# Motor-Y.net
KiCad netlist of a schematic drawn in Altium Designer
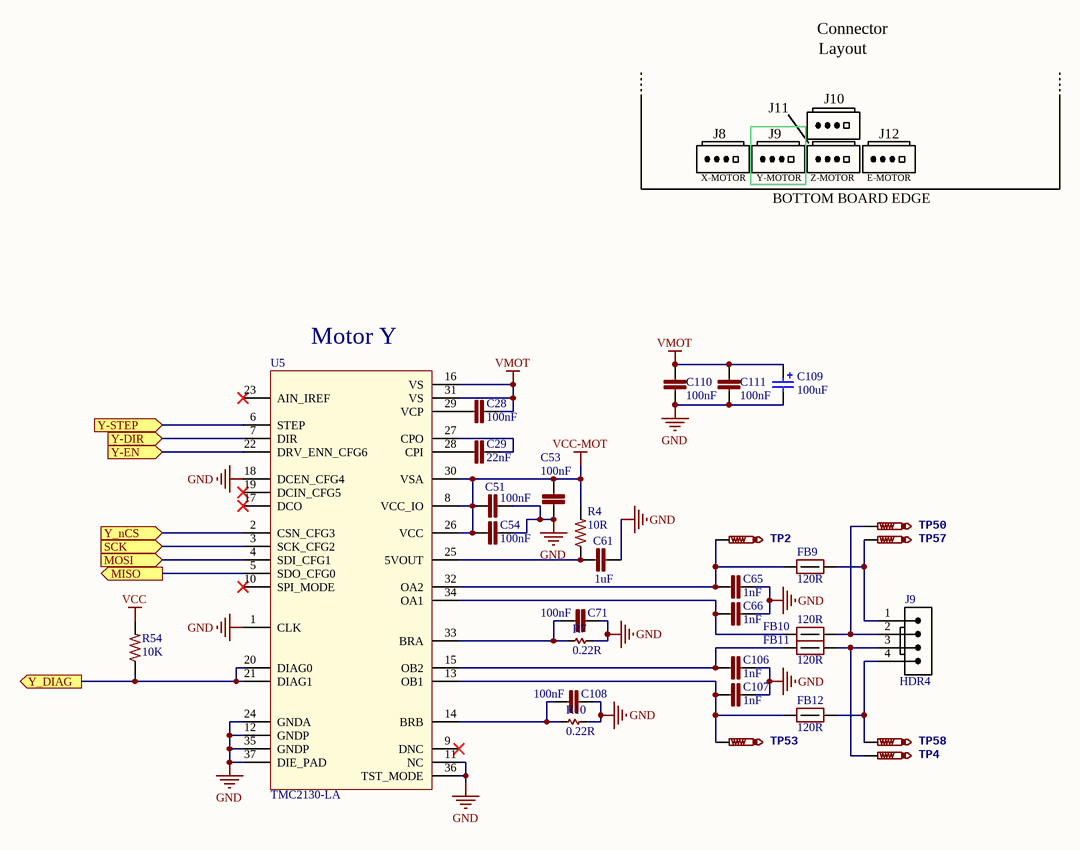
[diagram p0: Motor-Y.SchDoc]

(export (version "E")
  (design (tool "Eeschema 10.0.6"))
  (components
    (comp (ref "C28")
      (value "100nF")
      (footprint "C0603")
      (description "CAP CER 0603 100nF 50V 10% X7R")
      (fields (field (name "MANUFACTURER") "Kemet") (field (name "TOLERANCE") "+/- 10%"))
      (libsource (lib "") (part "C0603C104K5RACTU_2"))
    )
    (comp (ref "C29")
      (value "22nF")
      (footprint "C0402")
      (description "CAP CER 0402 22nF ±10% 50V X7R")
      (fields (field (name "MANUFACTURER") "YAGEO") (field (name "TOLERANCE") "+/- 10%"))
      (libsource (lib "3Delight") (part "GCM155R71H223KA55D"))
    )
    (comp (ref "C51")
      (value "100nF")
      (footprint "C0402")
      (description "CAP CER 0402 100nF 16V 10% X7R")
      (fields (field (name "MANUFACTURER") "Murata") (field (name "TOLERANCE") "+/- 10%"))
      (libsource (lib "3Delight") (part "GRM155R71C104KA88D"))
    )
    (comp (ref "C53")
      (value "100nF")
      (footprint "C0402")
      (description "CAP CER 0402 100nF 16V 10% X7R")
      (fields (field (name "MANUFACTURER") "Murata") (field (name "TOLERANCE") "+/- 10%"))
      (libsource (lib "") (part "GRM155R71C104KA88D_1"))
    )
    (comp (ref "C54")
      (value "100nF")
      (footprint "C0402")
      (description "CAP CER 0402 100nF 16V 10% X7R")
      (fields (field (name "MANUFACTURER") "Murata") (field (name "TOLERANCE") "+/- 10%"))
      (libsource (lib "3Delight") (part "GRM155R71C104KA88D"))
    )
    (comp (ref "C61")
      (value "1uF")
      (footprint "C0402")
      (description "CAP CER 0402 1uF 6.3V 10% X5R")
      (fields (field (name "MANUFACTURER") "Murata") (field (name "TOLERANCE") "+/- 10%"))
      (libsource (lib "3Delight") (part "GRM155R60J105KE19D"))
    )
    (comp (ref "C65")
      (value "1nF")
      (footprint "C0603")
      (description "CAP CER 0603  1nF 50v 10% X7R")
      (fields (field (name "MANUFACTURER") "Kemet") (field (name "TOLERANCE") "+/- 10%"))
      (libsource (lib "3Delight") (part "C0603C102K5RACTU"))
    )
    (comp (ref "C66")
      (value "1nF")
      (footprint "C0603")
      (description "CAP CER 0603  1nF 50v 10% X7R")
      (fields (field (name "MANUFACTURER") "Kemet") (field (name "TOLERANCE") "+/- 10%"))
      (libsource (lib "3Delight") (part "C0603C102K5RACTU"))
    )
    (comp (ref "C71")
      (value "100nF")
      (footprint "C0603")
      (description "CAP CER 0603 100nF 50V 10% X7R")
      (fields (field (name "MANUFACTURER") "Kemet") (field (name "TOLERANCE") "+/- 10%"))
      (libsource (lib "") (part "C0603C104K5RACTU_1"))
    )
    (comp (ref "C106")
      (value "1nF")
      (footprint "C0603")
      (description "CAP CER 0603  1nF 50v 10% X7R")
      (fields (field (name "MANUFACTURER") "Kemet") (field (name "TOLERANCE") "+/- 10%"))
      (libsource (lib "3Delight") (part "C0603C102K5RACTU"))
    )
    (comp (ref "C107")
      (value "1nF")
      (footprint "C0603")
      (description "CAP CER 0603  1nF 50v 10% X7R")
      (fields (field (name "MANUFACTURER") "Kemet") (field (name "TOLERANCE") "+/- 10%"))
      (libsource (lib "3Delight") (part "C0603C102K5RACTU"))
    )
    (comp (ref "C108")
      (value "100nF")
      (footprint "C0603")
      (description "CAP CER 0603 100nF 50V 10% X7R")
      (fields (field (name "MANUFACTURER") "Kemet") (field (name "TOLERANCE") "+/- 10%"))
      (libsource (lib "") (part "C0603C104K5RACTU_1"))
    )
    (comp (ref "C109")
      (value "100uF")
      (footprint "CAP-ELEC-063063077")
      (description "CAP ALUM 100UF 35V 20% SMD")
      (fields (field (name "MANUFACTURER") "Nichicon") (field (name "TOLERANCE") "+/- 20%"))
      (libsource (lib "3Delight") (part "UWT1V101MCL1GS"))
    )
    (comp (ref "C110")
      (value "100nF")
      (footprint "C0603")
      (description "CAP CER 0603 100nF 50V 10% X7R")
      (fields (field (name "MANUFACTURER") "Kemet") (field (name "TOLERANCE") "+/- 10%"))
      (libsource (lib "3Delight") (part "C0603C104K5RACTU"))
    )
    (comp (ref "C111")
      (value "100nF")
      (footprint "C0603")
      (description "CAP CER 0603 100nF 50V 10% X7R")
      (fields (field (name "MANUFACTURER") "Kemet") (field (name "TOLERANCE") "+/- 10%"))
      (libsource (lib "3Delight") (part "C0603C104K5RACTU"))
    )
    (comp (ref "FB9")
      (value "120R")
      (footprint "FB0603")
      (description "FERRITE BEAD 120 OHM 0603 1LN")
      (fields (field (name "MANUFACTURER") "Samsung") (field (name "PART") "FERRITE 120R 3A 0603"))
      (libsource (lib "Inductors") (part "FERRITE 120R 3A 0603"))
    )
    (comp (ref "FB10")
      (value "120R")
      (footprint "FB0603")
      (description "FERRITE BEAD 120 OHM 0603 1LN")
      (fields (field (name "MANUFACTURER") "Samsung") (field (name "PART") "FERRITE 120R 3A 0603"))
      (libsource (lib "Inductors") (part "FERRITE 120R 3A 0603"))
    )
    (comp (ref "FB11")
      (value "120R")
      (footprint "FB0603")
      (description "FERRITE BEAD 120 OHM 0603 1LN")
      (fields (field (name "MANUFACTURER") "Samsung") (field (name "PART") "FERRITE 120R 3A 0603"))
      (libsource (lib "Inductors") (part "FERRITE 120R 3A 0603"))
    )
    (comp (ref "FB12")
      (value "120R")
      (footprint "FB0603")
      (description "FERRITE BEAD 120 OHM 0603 1LN")
      (fields (field (name "MANUFACTURER") "Samsung") (field (name "PART") "FERRITE 120R 3A 0603"))
      (libsource (lib "Inductors") (part "FERRITE 120R 3A 0603"))
    )
    (comp (ref "J9")
      (value "HDR4")
      (footprint "4POL254")
      (description "Molex 4 Pin Clip Connector")
      (fields (field (name "MANUFACTURER") "Molex") (field (name "PART") "4 Pin Conn"))
      (libsource (lib "3Delight") (part "CONN 4PIN 0.1{dblquote} VERT SHRD LOCK ALT"))
    )
    (comp (ref "R4")
      (value "10R")
      (footprint "R0402")
      (description "RES SMD 10 OHM 1% 1/16W 0402")
      (fields (field (name "MANUFACTURER") "Yageo") (field (name "TOLERANCE") "+/- 1%"))
      (libsource (lib "3Delight") (part "RC0402FR-0710RL"))
    )
    (comp (ref "R7")
      (value "0.22R")
      (footprint "R1206")
      (description "RES SMD 0.22 OHM 1% 1/3W 1206")
      (fields (field (name "MANUFACTURER") "Panasonic") (field (name "TOLERANCE") "+/- 1%"))
      (libsource (lib "Resistors") (part "0.22R 1% 1206"))
    )
    (comp (ref "R10")
      (value "0.22R")
      (footprint "R1206")
      (description "RES SMD 0.22 OHM 1% 1/3W 1206")
      (fields (field (name "MANUFACTURER") "Panasonic") (field (name "TOLERANCE") "+/- 1%"))
      (libsource (lib "Resistors") (part "0.22R 1% 1206"))
    )
    (comp (ref "R54")
      (value "10K")
      (footprint "R0402")
      (description "RES SMD 10K OHM 1% 1/16W 0402")
      (fields (field (name "MANUFACTURER") "Yageo") (field (name "PART") "10k 1% 0402"))
      (libsource (lib "3Delight") (part "RC0402FR-0710KP"))
    )
    (comp (ref "TP2")
      (value "TestPoint")
      (footprint "TP1-27")
      (description "Test Point")
      (libsource (lib "3Delight") (part "TestPoint"))
    )
    (comp (ref "TP4")
      (value "TestPoint")
      (footprint "TP1-27")
      (description "Test Point")
      (libsource (lib "3Delight") (part "TestPoint"))
    )
    (comp (ref "TP50")
      (value "TestPoint")
      (footprint "TP1-27")
      (description "Test Point")
      (libsource (lib "3Delight") (part "TestPoint"))
    )
    (comp (ref "TP53")
      (value "TestPoint")
      (footprint "TP1-27")
      (description "Test Point")
      (libsource (lib "3Delight") (part "TestPoint"))
    )
    (comp (ref "TP57")
      (value "TestPoint")
      (footprint "TP1-27")
      (description "Test Point")
      (libsource (lib "3Delight") (part "TestPoint"))
    )
    (comp (ref "TP58")
      (value "TestPoint")
      (footprint "TP1-27")
      (description "Test Point")
      (libsource (lib "3Delight") (part "TestPoint"))
    )
    (comp (ref "U5")
      (value "TMC2130-LA")
      (footprint "QFN36-50P500X600X900_HS-37N")
      (description "IC STEPPER MOTOR DVR SPI 36QFN")
      (fields (field (name "MANUFACTURER") "Trinamic") (field (name "PART") "TMC2130"))
      (libsource (lib "3Delight") (part "TMC2130-LA-T"))
    )
  )
  (nets
    (net (code "1") (name "/MISO") (class "Default")
      (node (ref "U5") (pin "5") (pinfunction "SDO_CFG0_5") (pintype "passive"))
    )
    (net (code "2") (name "/MOSI") (class "Default")
      (node (ref "U5") (pin "4") (pinfunction "SDI_CFG1_4") (pintype "passive"))
    )
    (net (code "3") (name "/SCK") (class "Default")
      (node (ref "U5") (pin "3") (pinfunction "SCK_CFG2_3") (pintype "passive"))
    )
    (net (code "4") (name "/Y-DIR") (class "Default")
      (node (ref "U5") (pin "7") (pinfunction "DIR_7") (pintype "passive"))
    )
    (net (code "5") (name "/Y-EN") (class "Default")
      (node (ref "U5") (pin "22") (pinfunction "DRV_ENN_CFG6_22") (pintype "passive"))
    )
    (net (code "6") (name "/Y-STEP") (class "Default")
      (node (ref "U5") (pin "6") (pinfunction "STEP_6") (pintype "passive"))
    )
    (net (code "7") (name "/Y_DIAG") (class "Default")
      (node (ref "R54") (pin "1") (pinfunction "1_1") (pintype "passive"))
      (node (ref "U5") (pin "20") (pinfunction "DIAG0_20") (pintype "passive"))
      (node (ref "U5") (pin "21") (pinfunction "DIAG1_21") (pintype "passive"))
    )
    (net (code "8") (name "/Y_nCS") (class "Default")
      (node (ref "U5") (pin "2") (pinfunction "CSN_CFG3_2") (pintype "passive"))
    )
    (net (code "9") (name "GND") (class "Default")
      (node (ref "C106") (pin "2") (pinfunction "2_2") (pintype "passive"))
      (node (ref "C107") (pin "2") (pinfunction "2_2") (pintype "passive"))
      (node (ref "C108") (pin "1") (pinfunction "1_1") (pintype "passive"))
      (node (ref "C109") (pin "2") (pinfunction "2_2") (pintype "passive"))
      (node (ref "C110") (pin "1") (pinfunction "1_1") (pintype "passive"))
      (node (ref "C111") (pin "1") (pinfunction "1_1") (pintype "passive"))
      (node (ref "C51") (pin "1") (pinfunction "1_1") (pintype "passive"))
      (node (ref "C53") (pin "1") (pinfunction "1_1") (pintype "passive"))
      (node (ref "C54") (pin "1") (pinfunction "1_1") (pintype "passive"))
      (node (ref "C61") (pin "2") (pinfunction "2_2") (pintype "passive"))
      (node (ref "C65") (pin "2") (pinfunction "2_2") (pintype "passive"))
      (node (ref "C66") (pin "2") (pinfunction "2_2") (pintype "passive"))
      (node (ref "C71") (pin "1") (pinfunction "1_1") (pintype "passive"))
      (node (ref "R10") (pin "2") (pinfunction "2_2") (pintype "passive"))
      (node (ref "R7") (pin "2") (pinfunction "2_2") (pintype "passive"))
      (node (ref "U5") (pin "1") (pinfunction "CLK_1") (pintype "passive"))
      (node (ref "U5") (pin "11") (pinfunction "NC_11") (pintype "passive"))
      (node (ref "U5") (pin "12") (pinfunction "GNDP_12") (pintype "passive"))
      (node (ref "U5") (pin "18") (pinfunction "DCEN_CFG4_18") (pintype "passive"))
      (node (ref "U5") (pin "24") (pinfunction "GNDA_24") (pintype "passive"))
      (node (ref "U5") (pin "35") (pinfunction "GNDP_35") (pintype "passive"))
      (node (ref "U5") (pin "36") (pinfunction "TST_MODE_36") (pintype "passive"))
      (node (ref "U5") (pin "37") (pinfunction "DIE_PAD_37") (pintype "passive"))
    )
    (net (code "10") (name "Net-(FB9-Pad2)") (class "Default")
      (node (ref "FB9") (pin "2") (pinfunction "2_2") (pintype "passive"))
      (node (ref "J9") (pin "1") (pinfunction "1_1") (pintype "passive"))
      (node (ref "TP57") (pin "TP") (pinfunction "TP_TP") (pintype "passive"))
    )
    (net (code "11") (name "Net-(FB10-Pad2)") (class "Default")
      (node (ref "FB10") (pin "2") (pinfunction "2_2") (pintype "passive"))
      (node (ref "J9") (pin "2") (pinfunction "2_2") (pintype "passive"))
      (node (ref "TP50") (pin "TP") (pinfunction "TP_TP") (pintype "passive"))
    )
    (net (code "12") (name "Net-(FB11-Pad2)") (class "Default")
      (node (ref "FB11") (pin "2") (pinfunction "2_2") (pintype "passive"))
      (node (ref "J9") (pin "3") (pinfunction "3_3") (pintype "passive"))
      (node (ref "TP4") (pin "TP") (pinfunction "TP_TP") (pintype "passive"))
    )
    (net (code "13") (name "Net-(FB12-Pad2)") (class "Default")
      (node (ref "FB12") (pin "2") (pinfunction "2_2") (pintype "passive"))
      (node (ref "J9") (pin "4") (pinfunction "4_4") (pintype "passive"))
      (node (ref "TP58") (pin "TP") (pinfunction "TP_TP") (pintype "passive"))
    )
    (net (code "14") (name "Net-(U5-5VOUT)") (class "Default")
      (node (ref "C61") (pin "1") (pinfunction "1_1") (pintype "passive"))
      (node (ref "R4") (pin "1") (pinfunction "1_1") (pintype "passive"))
      (node (ref "U5") (pin "25") (pinfunction "5VOUT_25") (pintype "passive"))
    )
    (net (code "15") (name "Net-(U5-BRA)") (class "Default")
      (node (ref "C71") (pin "2") (pinfunction "2_2") (pintype "passive"))
      (node (ref "R7") (pin "1") (pinfunction "1_1") (pintype "passive"))
      (node (ref "U5") (pin "33") (pinfunction "BRA_33") (pintype "passive"))
    )
    (net (code "16") (name "Net-(U5-BRB)") (class "Default")
      (node (ref "C108") (pin "2") (pinfunction "2_2") (pintype "passive"))
      (node (ref "R10") (pin "1") (pinfunction "1_1") (pintype "passive"))
      (node (ref "U5") (pin "14") (pinfunction "BRB_14") (pintype "passive"))
    )
    (net (code "17") (name "Net-(U5-CPI)") (class "Default")
      (node (ref "C29") (pin "1") (pinfunction "1_1") (pintype "passive"))
      (node (ref "U5") (pin "28") (pinfunction "CPI_28") (pintype "passive"))
    )
    (net (code "18") (name "Net-(U5-CPO)") (class "Default")
      (node (ref "C29") (pin "2") (pinfunction "2_2") (pintype "passive"))
      (node (ref "U5") (pin "27") (pinfunction "CPO_27") (pintype "passive"))
    )
    (net (code "19") (name "Net-(U5-OA1)") (class "Default")
      (node (ref "C66") (pin "1") (pinfunction "1_1") (pintype "passive"))
      (node (ref "FB10") (pin "1") (pinfunction "1_1") (pintype "passive"))
      (node (ref "U5") (pin "34") (pinfunction "OA1_34") (pintype "passive"))
    )
    (net (code "20") (name "Net-(U5-OA2)") (class "Default")
      (node (ref "C65") (pin "1") (pinfunction "1_1") (pintype "passive"))
      (node (ref "FB9") (pin "1") (pinfunction "1_1") (pintype "passive"))
      (node (ref "TP2") (pin "TP") (pinfunction "TP_TP") (pintype "passive"))
      (node (ref "U5") (pin "32") (pinfunction "OA2_32") (pintype "passive"))
    )
    (net (code "21") (name "Net-(U5-OB1)") (class "Default")
      (node (ref "C107") (pin "1") (pinfunction "1_1") (pintype "passive"))
      (node (ref "FB12") (pin "1") (pinfunction "1_1") (pintype "passive"))
      (node (ref "TP53") (pin "TP") (pinfunction "TP_TP") (pintype "passive"))
      (node (ref "U5") (pin "13") (pinfunction "OB1_13") (pintype "passive"))
    )
    (net (code "22") (name "Net-(U5-OB2)") (class "Default")
      (node (ref "C106") (pin "1") (pinfunction "1_1") (pintype "passive"))
      (node (ref "FB11") (pin "1") (pinfunction "1_1") (pintype "passive"))
      (node (ref "U5") (pin "15") (pinfunction "OB2_15") (pintype "passive"))
    )
    (net (code "23") (name "Net-(U5-VCP)") (class "Default")
      (node (ref "C28") (pin "1") (pinfunction "1_1") (pintype "passive"))
      (node (ref "U5") (pin "29") (pinfunction "VCP_29") (pintype "passive"))
    )
    (net (code "24") (name "VCC") (class "Default")
      (node (ref "R54") (pin "2") (pinfunction "2_2") (pintype "passive"))
    )
    (net (code "25") (name "VCC-MOT") (class "Default")
      (node (ref "C51") (pin "2") (pinfunction "2_2") (pintype "passive"))
      (node (ref "C53") (pin "2") (pinfunction "2_2") (pintype "passive"))
      (node (ref "C54") (pin "2") (pinfunction "2_2") (pintype "passive"))
      (node (ref "R4") (pin "2") (pinfunction "2_2") (pintype "passive"))
      (node (ref "U5") (pin "26") (pinfunction "VCC_26") (pintype "passive"))
      (node (ref "U5") (pin "30") (pinfunction "VSA_30") (pintype "passive"))
      (node (ref "U5") (pin "8") (pinfunction "VCC_IO_8") (pintype "passive"))
    )
    (net (code "26") (name "VMOT") (class "Default")
      (node (ref "C109") (pin "1") (pinfunction "1_1") (pintype "passive"))
      (node (ref "C110") (pin "2") (pinfunction "2_2") (pintype "passive"))
      (node (ref "C111") (pin "2") (pinfunction "2_2") (pintype "passive"))
      (node (ref "C28") (pin "2") (pinfunction "2_2") (pintype "passive"))
      (node (ref "U5") (pin "16") (pinfunction "VS_16") (pintype "passive"))
      (node (ref "U5") (pin "31") (pinfunction "VS_31") (pintype "passive"))
    )
    (net (code "27") (name "unconnected-(U5-AIN_IREF-Pad23)") (class "Default")
      (node (ref "U5") (pin "23") (pinfunction "AIN_IREF_23") (pintype "passive+no_connect"))
    )
    (net (code "28") (name "unconnected-(U5-DCIN_CFG5-Pad19)") (class "Default")
      (node (ref "U5") (pin "19") (pinfunction "DCIN_CFG5_19") (pintype "passive+no_connect"))
    )
    (net (code "29") (name "unconnected-(U5-DCO-Pad17)") (class "Default")
      (node (ref "U5") (pin "17") (pinfunction "DCO_17") (pintype "passive+no_connect"))
    )
    (net (code "30") (name "unconnected-(U5-DNC-Pad9)") (class "Default")
      (node (ref "U5") (pin "9") (pinfunction "DNC_9") (pintype "passive+no_connect"))
    )
    (net (code "31") (name "unconnected-(U5-SPI_MODE-Pad10)") (class "Default")
      (node (ref "U5") (pin "10") (pinfunction "SPI_MODE_10") (pintype "passive+no_connect"))
    )
  )
)
